# hollis_omnidrive.net
KiCad netlist of a schematic drawn in EAGLE
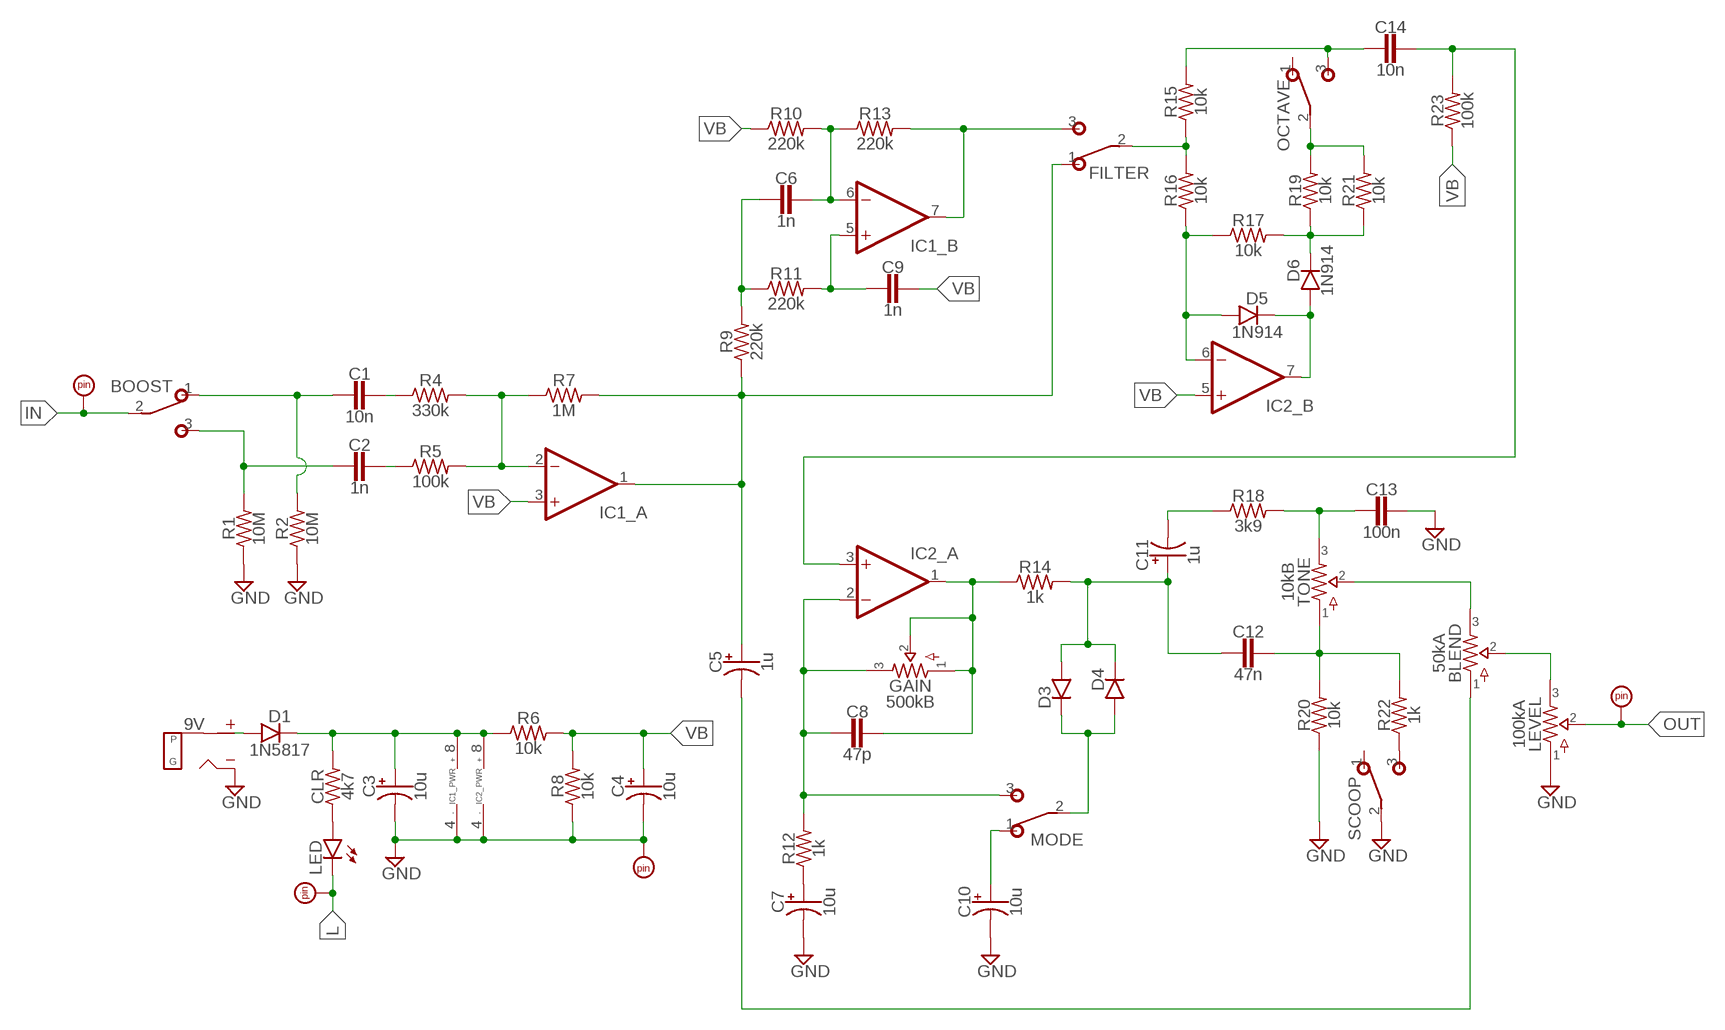
[diagram p0: schematic, sheet 1]

(export (version "E")
  (design (tool "Eeschema 10.0.6"))
  (components
    (comp (ref "9V")
      (value "DC_MONO")
      (footprint "eagle-import:DC")
      (libsource (lib "eagle-import") (part "DC_MONO"))
    )
    (comp (ref "BLEND")
      (value "50kA")
      (footprint "eagle-import:16MM")
      (libsource (lib "eagle-import") (part "POTS16MM"))
    )
    (comp (ref "BOOST")
      (value "SPDT")
      (footprint "eagle-import:M9040P")
      (libsource (lib "eagle-import") (part "SPDT"))
    )
    (comp (ref "C1")
      (value "10n")
      (footprint "eagle-import:050X030_025_2")
      (libsource (lib "eagle-import") (part "CER/FILM2"))
    )
    (comp (ref "C2")
      (value "1n")
      (footprint "eagle-import:050X030_025_2")
      (libsource (lib "eagle-import") (part "CER/FILM2"))
    )
    (comp (ref "C3")
      (value "10u")
      (footprint "eagle-import:050_020_1")
      (libsource (lib "eagle-import") (part "0501"))
    )
    (comp (ref "C4")
      (value "10u")
      (footprint "eagle-import:050_020_1")
      (libsource (lib "eagle-import") (part "0501"))
    )
    (comp (ref "C5")
      (value "1u")
      (footprint "eagle-import:050_020_1")
      (libsource (lib "eagle-import") (part "0501"))
    )
    (comp (ref "C6")
      (value "1n")
      (footprint "eagle-import:050X030_025_2")
      (libsource (lib "eagle-import") (part "CER/FILM2"))
    )
    (comp (ref "C7")
      (value "10u")
      (footprint "eagle-import:050_020_1")
      (libsource (lib "eagle-import") (part "0501"))
    )
    (comp (ref "C8")
      (value "47p")
      (footprint "eagle-import:050X030_025_2")
      (libsource (lib "eagle-import") (part "CER/FILM2"))
    )
    (comp (ref "C9")
      (value "1n")
      (footprint "eagle-import:050X030_025_2")
      (libsource (lib "eagle-import") (part "CER/FILM2"))
    )
    (comp (ref "C10")
      (value "10u")
      (footprint "eagle-import:050_020_1")
      (libsource (lib "eagle-import") (part "0501"))
    )
    (comp (ref "C11")
      (value "1u")
      (footprint "eagle-import:050_020_1")
      (libsource (lib "eagle-import") (part "0501"))
    )
    (comp (ref "C12")
      (value "47n")
      (footprint "eagle-import:050X030_025_2")
      (libsource (lib "eagle-import") (part "CER/FILM2"))
    )
    (comp (ref "C13")
      (value "100n")
      (footprint "eagle-import:050X030_025_2")
      (libsource (lib "eagle-import") (part "CER/FILM2"))
    )
    (comp (ref "C14")
      (value "10n")
      (footprint "eagle-import:050X030_025_2")
      (libsource (lib "eagle-import") (part "CER/FILM2"))
    )
    (comp (ref "CLR")
      (value "4k7")
      (footprint "eagle-import:R0207_3")
      (libsource (lib "eagle-import") (part "R_.3B"))
    )
    (comp (ref "D1")
      (value "1N5817")
      (footprint "eagle-import:DO41-3")
      (libsource (lib "eagle-import") (part "DO41.3"))
    )
    (comp (ref "D3")
      (value "DO35.3")
      (footprint "eagle-import:DO35-3")
      (libsource (lib "eagle-import") (part "DO35.3"))
    )
    (comp (ref "D4")
      (value "DO35.3")
      (footprint "eagle-import:DO35-3")
      (libsource (lib "eagle-import") (part "DO35.3"))
    )
    (comp (ref "D5")
      (value "1N914")
      (footprint "eagle-import:DO35-2")
      (libsource (lib "eagle-import") (part "DO35.2"))
    )
    (comp (ref "D6")
      (value "1N914")
      (footprint "eagle-import:DO35-2")
      (libsource (lib "eagle-import") (part "DO35.2"))
    )
    (comp (ref "FILTER")
      (value "SPDT")
      (footprint "eagle-import:M9040P")
      (libsource (lib "eagle-import") (part "SPDT"))
    )
    (comp (ref "GAIN")
      (value "500kB")
      (footprint "eagle-import:16MM")
      (libsource (lib "eagle-import") (part "POTS16MM"))
    )
    (comp (ref "GND")
      (value "PADRND")
      (footprint "eagle-import:ROUND")
      (libsource (lib "eagle-import") (part "PADRND"))
    )
    (comp (ref "IC1")
      (value "DUALTH")
      (footprint "eagle-import:DIL08")
      (libsource (lib "eagle-import") (part "DUALTH"))
    )
    (comp (ref "IC2")
      (value "DUALTH")
      (footprint "eagle-import:DIL08")
      (libsource (lib "eagle-import") (part "DUALTH"))
    )
    (comp (ref "IN")
      (value "PADSQR")
      (footprint "eagle-import:SQUARE")
      (libsource (lib "eagle-import") (part "PADSQR"))
    )
    (comp (ref "L")
      (value "PADRND")
      (footprint "eagle-import:ROUND")
      (libsource (lib "eagle-import") (part "PADRND"))
    )
    (comp (ref "LED")
      (value "LEDB")
      (footprint "eagle-import:3MM_B")
      (libsource (lib "eagle-import") (part "LEDB"))
    )
    (comp (ref "LEVEL")
      (value "100kA")
      (footprint "eagle-import:16MM")
      (libsource (lib "eagle-import") (part "POTS16MM"))
    )
    (comp (ref "MODE")
      (value "SPDT")
      (footprint "eagle-import:M9040P")
      (libsource (lib "eagle-import") (part "SPDT"))
    )
    (comp (ref "OCTAVE")
      (value "SPDT")
      (footprint "eagle-import:M9040P")
      (libsource (lib "eagle-import") (part "SPDT"))
    )
    (comp (ref "OUT")
      (value "PADSQR")
      (footprint "eagle-import:SQUARE")
      (libsource (lib "eagle-import") (part "PADSQR"))
    )
    (comp (ref "R1")
      (value "10M")
      (footprint "eagle-import:R0207_3")
      (libsource (lib "eagle-import") (part "R_.3B"))
    )
    (comp (ref "R2")
      (value "10M")
      (footprint "eagle-import:R0207_3")
      (libsource (lib "eagle-import") (part "R_.3B"))
    )
    (comp (ref "R4")
      (value "330k")
      (footprint "eagle-import:R0207_3")
      (libsource (lib "eagle-import") (part "R_.3B"))
    )
    (comp (ref "R5")
      (value "100k")
      (footprint "eagle-import:R0207_3")
      (libsource (lib "eagle-import") (part "R_.3B"))
    )
    (comp (ref "R6")
      (value "10k")
      (footprint "eagle-import:R0207_3")
      (libsource (lib "eagle-import") (part "R_.3B"))
    )
    (comp (ref "R7")
      (value "1M")
      (footprint "eagle-import:R0207_3")
      (libsource (lib "eagle-import") (part "R_.3B"))
    )
    (comp (ref "R8")
      (value "10k")
      (footprint "eagle-import:R0207_3")
      (libsource (lib "eagle-import") (part "R_.3B"))
    )
    (comp (ref "R9")
      (value "220k")
      (footprint "eagle-import:R0207_3")
      (libsource (lib "eagle-import") (part "R_.3B"))
    )
    (comp (ref "R10")
      (value "220k")
      (footprint "eagle-import:R0207_3")
      (libsource (lib "eagle-import") (part "R_.3B"))
    )
    (comp (ref "R11")
      (value "220k")
      (footprint "eagle-import:R0207_3")
      (libsource (lib "eagle-import") (part "R_.3B"))
    )
    (comp (ref "R12")
      (value "1k")
      (footprint "eagle-import:R0207_3")
      (libsource (lib "eagle-import") (part "R_.3B"))
    )
    (comp (ref "R13")
      (value "220k")
      (footprint "eagle-import:R0207_3")
      (libsource (lib "eagle-import") (part "R_.3B"))
    )
    (comp (ref "R14")
      (value "1k")
      (footprint "eagle-import:R0207_3")
      (libsource (lib "eagle-import") (part "R_.3B"))
    )
    (comp (ref "R15")
      (value "10k")
      (footprint "eagle-import:R0207_3")
      (libsource (lib "eagle-import") (part "R_.3B"))
    )
    (comp (ref "R16")
      (value "10k")
      (footprint "eagle-import:R0207_3")
      (libsource (lib "eagle-import") (part "R_.3B"))
    )
    (comp (ref "R17")
      (value "10k")
      (footprint "eagle-import:R0207_3")
      (libsource (lib "eagle-import") (part "R_.3B"))
    )
    (comp (ref "R18")
      (value "3k9")
      (footprint "eagle-import:R0207_3")
      (libsource (lib "eagle-import") (part "R_.3B"))
    )
    (comp (ref "R19")
      (value "10k")
      (footprint "eagle-import:R0207_3")
      (libsource (lib "eagle-import") (part "R_.3B"))
    )
    (comp (ref "R20")
      (value "10k")
      (footprint "eagle-import:R0207_3")
      (libsource (lib "eagle-import") (part "R_.3B"))
    )
    (comp (ref "R21")
      (value "10k")
      (footprint "eagle-import:R0207_3")
      (libsource (lib "eagle-import") (part "R_.3B"))
    )
    (comp (ref "R22")
      (value "1k")
      (footprint "eagle-import:R0207_3")
      (libsource (lib "eagle-import") (part "R_.3B"))
    )
    (comp (ref "R23")
      (value "100k")
      (footprint "eagle-import:R0207_3")
      (libsource (lib "eagle-import") (part "R_.3B"))
    )
    (comp (ref "SCOOP")
      (value "SPDT")
      (footprint "eagle-import:M9040P")
      (libsource (lib "eagle-import") (part "SPDT"))
    )
    (comp (ref "TONE")
      (value "10kB")
      (footprint "eagle-import:16MM")
      (libsource (lib "eagle-import") (part "POTS16MM"))
    )
  )
  (nets
    (net (code "1") (name "GND") (class "Default")
      (node (ref "9V") (pin "S") (pinfunction "SLEEVE_S") (pintype "passive"))
      (node (ref "C10") (pin "-") (pinfunction "-_-") (pintype "passive"))
      (node (ref "C13") (pin "1") (pinfunction "1_1") (pintype "passive"))
      (node (ref "C3") (pin "-") (pinfunction "-_-") (pintype "passive"))
      (node (ref "C4") (pin "-") (pinfunction "-_-") (pintype "passive"))
      (node (ref "C7") (pin "-") (pinfunction "-_-") (pintype "passive"))
      (node (ref "GND") (pin "1") (pinfunction "P$1_1") (pintype "bidirectional"))
      (node (ref "IC1") (pin "4") (pinfunction "V-_4") (pintype "power_in"))
      (node (ref "IC2") (pin "4") (pinfunction "V-_4") (pintype "power_in"))
      (node (ref "LEVEL") (pin "1") (pinfunction "1_1") (pintype "passive"))
      (node (ref "R1") (pin "1") (pinfunction "1_1") (pintype "passive"))
      (node (ref "R2") (pin "1") (pinfunction "1_1") (pintype "passive"))
      (node (ref "R20") (pin "1") (pinfunction "1_1") (pintype "passive"))
      (node (ref "R8") (pin "1") (pinfunction "1_1") (pintype "passive"))
      (node (ref "SCOOP") (pin "2") (pinfunction "P_2") (pintype "passive"))
    )
    (net (code "2") (name "IN") (class "Default")
      (node (ref "BOOST") (pin "2") (pinfunction "P_2") (pintype "passive"))
      (node (ref "IN") (pin "1") (pinfunction "P$1_1") (pintype "bidirectional"))
    )
    (net (code "3") (name "L") (class "Default")
      (node (ref "L") (pin "1") (pinfunction "P$1_1") (pintype "bidirectional"))
      (node (ref "LED") (pin "K") (pinfunction "C_K") (pintype "passive"))
    )
    (net (code "4") (name "Net-(9V-TIP)") (class "Default")
      (node (ref "9V") (pin "T") (pinfunction "TIP_T") (pintype "passive"))
      (node (ref "D1") (pin "A") (pinfunction "A_A") (pintype "passive"))
    )
    (net (code "5") (name "Net-(BLEND-Pad1)") (class "Default")
      (node (ref "BLEND") (pin "1") (pinfunction "1_1") (pintype "passive"))
      (node (ref "C5") (pin "-") (pinfunction "-_-") (pintype "passive"))
    )
    (net (code "6") (name "Net-(BLEND-Pad2)") (class "Default")
      (node (ref "BLEND") (pin "2") (pinfunction "2_2") (pintype "passive"))
      (node (ref "LEVEL") (pin "3") (pinfunction "3_3") (pintype "passive"))
    )
    (net (code "7") (name "Net-(BLEND-Pad3)") (class "Default")
      (node (ref "BLEND") (pin "3") (pinfunction "3_3") (pintype "passive"))
      (node (ref "TONE") (pin "2") (pinfunction "2_2") (pintype "passive"))
    )
    (net (code "8") (name "Net-(BOOST-O)") (class "Default")
      (node (ref "BOOST") (pin "1") (pinfunction "O_1") (pintype "passive"))
      (node (ref "C1") (pin "2") (pinfunction "2_2") (pintype "passive"))
      (node (ref "R2") (pin "2") (pinfunction "2_2") (pintype "passive"))
    )
    (net (code "9") (name "Net-(BOOST-S)") (class "Default")
      (node (ref "BOOST") (pin "3") (pinfunction "S_3") (pintype "passive"))
      (node (ref "C2") (pin "2") (pinfunction "2_2") (pintype "passive"))
      (node (ref "R1") (pin "2") (pinfunction "2_2") (pintype "passive"))
    )
    (net (code "10") (name "Net-(C1-Pad1)") (class "Default")
      (node (ref "C1") (pin "1") (pinfunction "1_1") (pintype "passive"))
      (node (ref "R4") (pin "1") (pinfunction "1_1") (pintype "passive"))
    )
    (net (code "11") (name "Net-(C2-Pad1)") (class "Default")
      (node (ref "C2") (pin "1") (pinfunction "1_1") (pintype "passive"))
      (node (ref "R5") (pin "1") (pinfunction "1_1") (pintype "passive"))
    )
    (net (code "12") (name "Net-(C6-Pad2)") (class "Default")
      (node (ref "C6") (pin "2") (pinfunction "2_2") (pintype "passive"))
      (node (ref "R11") (pin "1") (pinfunction "1_1") (pintype "passive"))
      (node (ref "R9") (pin "2") (pinfunction "2_2") (pintype "passive"))
    )
    (net (code "13") (name "Net-(C7-Pad+)") (class "Default")
      (node (ref "C7") (pin "+") (pinfunction "+_+") (pintype "passive"))
      (node (ref "R12") (pin "1") (pinfunction "1_1") (pintype "passive"))
    )
    (net (code "14") (name "Net-(C11-Pad+)") (class "Default")
      (node (ref "C11") (pin "+") (pinfunction "+_+") (pintype "passive"))
      (node (ref "C12") (pin "2") (pinfunction "2_2") (pintype "passive"))
      (node (ref "D3") (pin "A") (pinfunction "A_A") (pintype "passive"))
      (node (ref "D4") (pin "C") (pinfunction "C_C") (pintype "passive"))
      (node (ref "R14") (pin "2") (pinfunction "2_2") (pintype "passive"))
    )
    (net (code "15") (name "Net-(C11-Pad-)") (class "Default")
      (node (ref "C11") (pin "-") (pinfunction "-_-") (pintype "passive"))
      (node (ref "R18") (pin "1") (pinfunction "1_1") (pintype "passive"))
    )
    (net (code "16") (name "Net-(C12-Pad1)") (class "Default")
      (node (ref "C12") (pin "1") (pinfunction "1_1") (pintype "passive"))
      (node (ref "R20") (pin "2") (pinfunction "2_2") (pintype "passive"))
      (node (ref "R22") (pin "2") (pinfunction "2_2") (pintype "passive"))
      (node (ref "TONE") (pin "1") (pinfunction "1_1") (pintype "passive"))
    )
    (net (code "17") (name "Net-(C13-Pad2)") (class "Default")
      (node (ref "C13") (pin "2") (pinfunction "2_2") (pintype "passive"))
      (node (ref "R18") (pin "2") (pinfunction "2_2") (pintype "passive"))
      (node (ref "TONE") (pin "3") (pinfunction "3_3") (pintype "passive"))
    )
    (net (code "18") (name "Net-(CLR-Pad1)") (class "Default")
      (node (ref "CLR") (pin "1") (pinfunction "1_1") (pintype "passive"))
      (node (ref "LED") (pin "A") (pinfunction "A_A") (pintype "passive"))
    )
    (net (code "19") (name "Net-(D6-PadC)") (class "Default")
      (node (ref "D6") (pin "C") (pinfunction "C_C") (pintype "passive"))
      (node (ref "R17") (pin "2") (pinfunction "2_2") (pintype "passive"))
      (node (ref "R19") (pin "1") (pinfunction "1_1") (pintype "passive"))
      (node (ref "R21") (pin "1") (pinfunction "1_1") (pintype "passive"))
    )
    (net (code "20") (name "Net-(FILTER-O)") (class "Default")
      (node (ref "C5") (pin "+") (pinfunction "+_+") (pintype "passive"))
      (node (ref "FILTER") (pin "1") (pinfunction "O_1") (pintype "passive"))
      (node (ref "IC1") (pin "1") (pinfunction "OUT_1") (pintype "output"))
      (node (ref "R7") (pin "2") (pinfunction "2_2") (pintype "passive"))
      (node (ref "R9") (pin "1") (pinfunction "1_1") (pintype "passive"))
    )
    (net (code "21") (name "Net-(FILTER-P)") (class "Default")
      (node (ref "FILTER") (pin "2") (pinfunction "P_2") (pintype "passive"))
      (node (ref "R15") (pin "1") (pinfunction "1_1") (pintype "passive"))
      (node (ref "R16") (pin "2") (pinfunction "2_2") (pintype "passive"))
    )
    (net (code "22") (name "Net-(FILTER-S)") (class "Default")
      (node (ref "FILTER") (pin "3") (pinfunction "S_3") (pintype "passive"))
      (node (ref "IC1") (pin "7") (pinfunction "OUT_7") (pintype "output"))
      (node (ref "R13") (pin "2") (pinfunction "2_2") (pintype "passive"))
    )
    (net (code "23") (name "Net-(IC1A--IN)") (class "Default")
      (node (ref "IC1") (pin "2") (pinfunction "-IN_2") (pintype "input"))
      (node (ref "R4") (pin "2") (pinfunction "2_2") (pintype "passive"))
      (node (ref "R5") (pin "2") (pinfunction "2_2") (pintype "passive"))
      (node (ref "R7") (pin "1") (pinfunction "1_1") (pintype "passive"))
    )
    (net (code "24") (name "Net-(IC1B-+IN)") (class "Default")
      (node (ref "C9") (pin "1") (pinfunction "1_1") (pintype "passive"))
      (node (ref "IC1") (pin "5") (pinfunction "+IN_5") (pintype "input"))
      (node (ref "R11") (pin "2") (pinfunction "2_2") (pintype "passive"))
    )
    (net (code "25") (name "Net-(IC1B--IN)") (class "Default")
      (node (ref "C6") (pin "1") (pinfunction "1_1") (pintype "passive"))
      (node (ref "IC1") (pin "6") (pinfunction "-IN_6") (pintype "input"))
      (node (ref "R10") (pin "2") (pinfunction "2_2") (pintype "passive"))
      (node (ref "R13") (pin "1") (pinfunction "1_1") (pintype "passive"))
    )
    (net (code "26") (name "Net-(IC1C-V+)") (class "Default")
      (node (ref "C3") (pin "+") (pinfunction "+_+") (pintype "passive"))
      (node (ref "CLR") (pin "2") (pinfunction "2_2") (pintype "passive"))
      (node (ref "D1") (pin "C") (pinfunction "C_C") (pintype "passive"))
      (node (ref "IC1") (pin "8") (pinfunction "V+_8") (pintype "power_in"))
      (node (ref "IC2") (pin "8") (pinfunction "V+_8") (pintype "power_in"))
      (node (ref "R6") (pin "1") (pinfunction "1_1") (pintype "passive"))
    )
    (net (code "27") (name "Net-(IC2A-+IN)") (class "Default")
      (node (ref "C14") (pin "1") (pinfunction "1_1") (pintype "passive"))
      (node (ref "IC2") (pin "3") (pinfunction "+IN_3") (pintype "input"))
      (node (ref "R23") (pin "2") (pinfunction "2_2") (pintype "passive"))
    )
    (net (code "28") (name "Net-(IC2A--IN)") (class "Default")
      (node (ref "C8") (pin "2") (pinfunction "2_2") (pintype "passive"))
      (node (ref "GAIN") (pin "3") (pinfunction "3_3") (pintype "passive"))
      (node (ref "IC2") (pin "2") (pinfunction "-IN_2") (pintype "input"))
      (node (ref "MODE") (pin "3") (pinfunction "S_3") (pintype "passive"))
      (node (ref "R12") (pin "2") (pinfunction "2_2") (pintype "passive"))
    )
    (net (code "29") (name "Net-(IC2A-OUT)") (class "Default")
      (node (ref "C8") (pin "1") (pinfunction "1_1") (pintype "passive"))
      (node (ref "GAIN") (pin "1") (pinfunction "1_1") (pintype "passive"))
      (node (ref "GAIN") (pin "2") (pinfunction "2_2") (pintype "passive"))
      (node (ref "IC2") (pin "1") (pinfunction "OUT_1") (pintype "output"))
      (node (ref "R14") (pin "1") (pinfunction "1_1") (pintype "passive"))
    )
    (net (code "30") (name "Net-(IC2B--IN)") (class "Default")
      (node (ref "D5") (pin "A") (pinfunction "A_A") (pintype "passive"))
      (node (ref "IC2") (pin "6") (pinfunction "-IN_6") (pintype "input"))
      (node (ref "R16") (pin "1") (pinfunction "1_1") (pintype "passive"))
      (node (ref "R17") (pin "1") (pinfunction "1_1") (pintype "passive"))
    )
    (net (code "31") (name "Net-(IC2B-OUT)") (class "Default")
      (node (ref "D5") (pin "C") (pinfunction "C_C") (pintype "passive"))
      (node (ref "D6") (pin "A") (pinfunction "A_A") (pintype "passive"))
      (node (ref "IC2") (pin "7") (pinfunction "OUT_7") (pintype "output"))
    )
    (net (code "32") (name "Net-(MODE-O)") (class "Default")
      (node (ref "C10") (pin "+") (pinfunction "+_+") (pintype "passive"))
      (node (ref "MODE") (pin "1") (pinfunction "O_1") (pintype "passive"))
    )
    (net (code "33") (name "Net-(MODE-P)") (class "Default")
      (node (ref "D3") (pin "C") (pinfunction "C_C") (pintype "passive"))
      (node (ref "D4") (pin "A") (pinfunction "A_A") (pintype "passive"))
      (node (ref "MODE") (pin "2") (pinfunction "P_2") (pintype "passive"))
    )
    (net (code "34") (name "Net-(OCTAVE-P)") (class "Default")
      (node (ref "OCTAVE") (pin "2") (pinfunction "P_2") (pintype "passive"))
      (node (ref "R19") (pin "2") (pinfunction "2_2") (pintype "passive"))
      (node (ref "R21") (pin "2") (pinfunction "2_2") (pintype "passive"))
    )
    (net (code "35") (name "Net-(OCTAVE-S)") (class "Default")
      (node (ref "C14") (pin "2") (pinfunction "2_2") (pintype "passive"))
      (node (ref "OCTAVE") (pin "3") (pinfunction "S_3") (pintype "passive"))
      (node (ref "R15") (pin "2") (pinfunction "2_2") (pintype "passive"))
    )
    (net (code "36") (name "Net-(SCOOP-S)") (class "Default")
      (node (ref "R22") (pin "1") (pinfunction "1_1") (pintype "passive"))
      (node (ref "SCOOP") (pin "3") (pinfunction "S_3") (pintype "passive"))
    )
    (net (code "37") (name "OUT") (class "Default")
      (node (ref "LEVEL") (pin "2") (pinfunction "2_2") (pintype "passive"))
      (node (ref "OUT") (pin "1") (pinfunction "P$1_1") (pintype "bidirectional"))
    )
    (net (code "38") (name "VB") (class "Default")
      (node (ref "C4") (pin "+") (pinfunction "+_+") (pintype "passive"))
      (node (ref "C9") (pin "2") (pinfunction "2_2") (pintype "passive"))
      (node (ref "IC1") (pin "3") (pinfunction "+IN_3") (pintype "input"))
      (node (ref "IC2") (pin "5") (pinfunction "+IN_5") (pintype "input"))
      (node (ref "R10") (pin "1") (pinfunction "1_1") (pintype "passive"))
      (node (ref "R23") (pin "1") (pinfunction "1_1") (pintype "passive"))
      (node (ref "R6") (pin "2") (pinfunction "2_2") (pintype "passive"))
      (node (ref "R8") (pin "2") (pinfunction "2_2") (pintype "passive"))
    )
    (net (code "39") (name "unconnected-(OCTAVE-O-Pad1)") (class "Default")
      (node (ref "OCTAVE") (pin "1") (pinfunction "O_1") (pintype "passive"))
    )
    (net (code "40") (name "unconnected-(SCOOP-O-Pad1)") (class "Default")
      (node (ref "SCOOP") (pin "1") (pinfunction "O_1") (pintype "passive"))
    )
  )
)
